# 432.net
KiCad netlist of a schematic drawn in Altium Designer
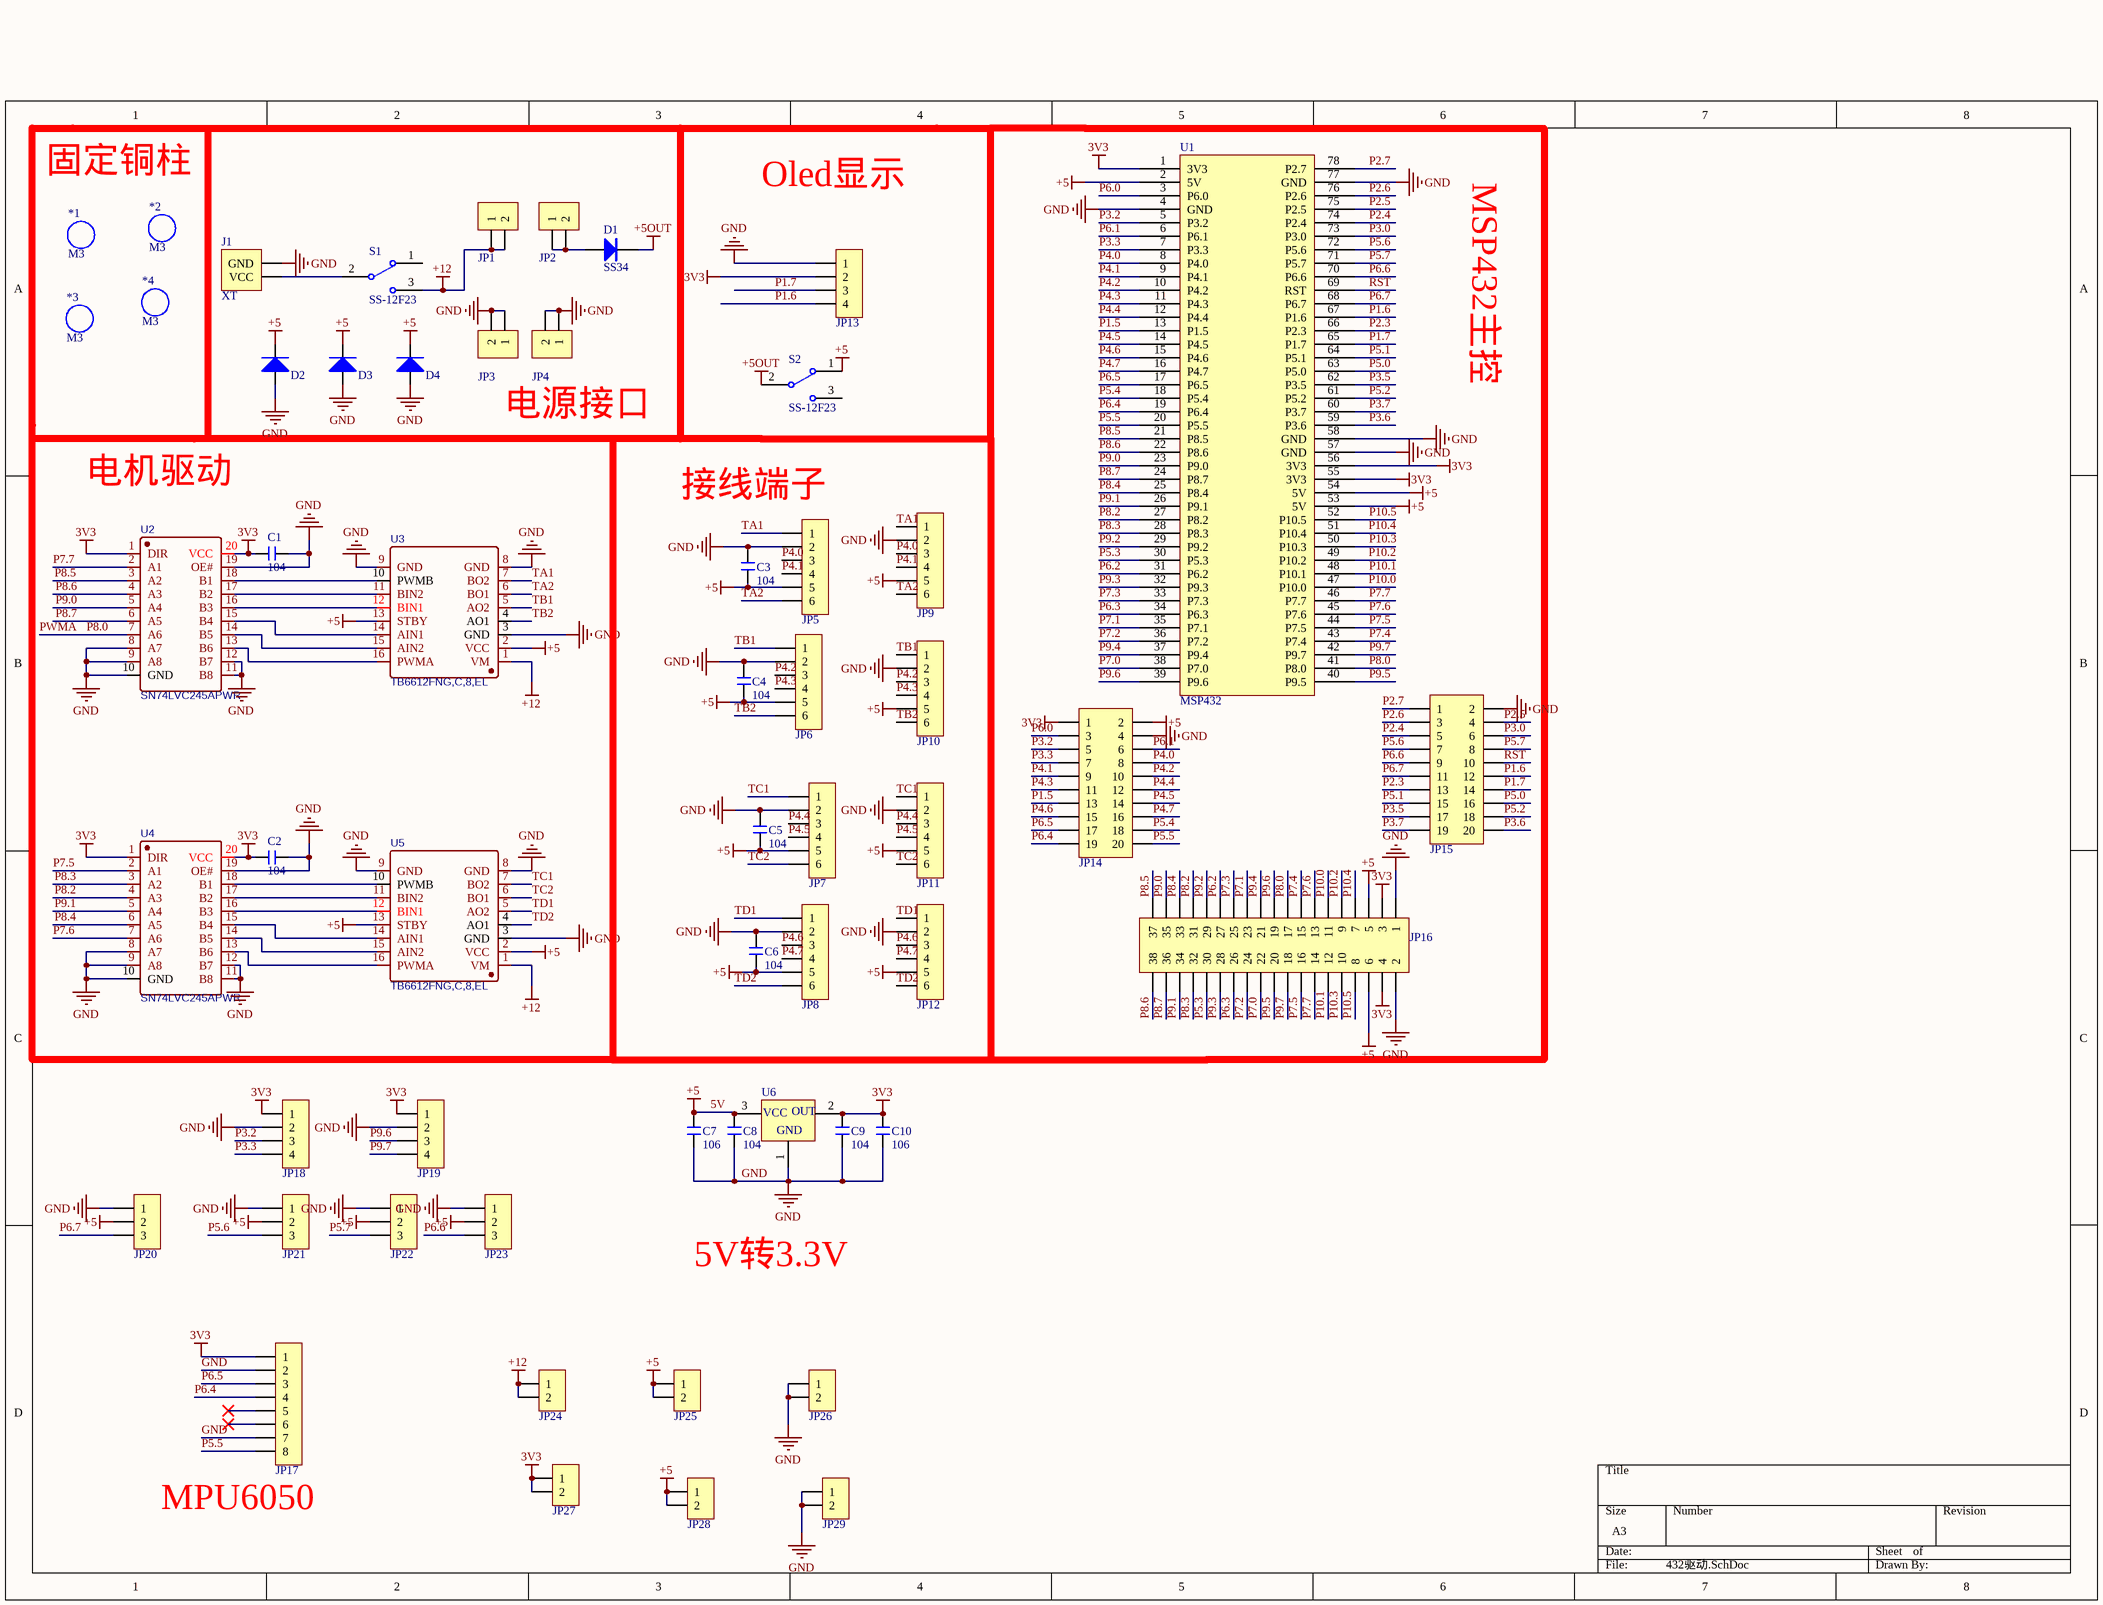
[diagram p0: 432驱动.SchDoc]

(export (version "E")
  (design (tool "Eeschema 10.0.6"))
  (components
    (comp (ref "*1")
      (value "M3")
      (footprint "M3 125X300")
      (description "铜柱孔")
      (fields (field (name "版权归属") "黎明电子style"))
      (libsource (lib "1.7.1-未分类器件") (part "M3"))
    )
    (comp (ref "*2")
      (value "M3")
      (footprint "M3 125X300")
      (description "铜柱孔")
      (fields (field (name "版权归属") "黎明电子style"))
      (libsource (lib "1.7.1-未分类器件") (part "M3"))
    )
    (comp (ref "*3")
      (value "M3")
      (footprint "M3 125X300")
      (description "铜柱孔")
      (fields (field (name "版权归属") "黎明电子style"))
      (libsource (lib "1.7.1-未分类器件") (part "M3"))
    )
    (comp (ref "*4")
      (value "M3")
      (footprint "M3 125X300")
      (description "铜柱孔")
      (fields (field (name "版权归属") "黎明电子style"))
      (libsource (lib "1.7.1-未分类器件") (part "M3"))
    )
    (comp (ref "C1")
      (value "104")
      (footprint "C 0603")
      (description "无极性贴片电容")
      (fields (field (name "版权归属") "黎明电子style"))
      (libsource (lib "1.3.2-电阻_电容_电感") (part "C"))
    )
    (comp (ref "C2")
      (value "104")
      (footprint "C 0603")
      (description "无极性贴片电容")
      (fields (field (name "版权归属") "黎明电子style"))
      (libsource (lib "1.3.2-电阻_电容_电感") (part "C"))
    )
    (comp (ref "C3")
      (value "104")
      (footprint "C 0603_M")
      (description "无极性贴片电容")
      (fields (field (name "版权归属") "黎明电子style"))
      (libsource (lib "1.3.2-电阻_电容_电感") (part "C"))
    )
    (comp (ref "C4")
      (value "104")
      (footprint "C 0603_M")
      (description "无极性贴片电容")
      (fields (field (name "版权归属") "黎明电子style"))
      (libsource (lib "1.3.2-电阻_电容_电感") (part "C"))
    )
    (comp (ref "C5")
      (value "104")
      (footprint "C 0603_M")
      (description "无极性贴片电容")
      (fields (field (name "版权归属") "黎明电子style"))
      (libsource (lib "1.3.2-电阻_电容_电感") (part "C"))
    )
    (comp (ref "C6")
      (value "104")
      (footprint "C 0603_M")
      (description "无极性贴片电容")
      (fields (field (name "版权归属") "黎明电子style"))
      (libsource (lib "1.3.2-电阻_电容_电感") (part "C"))
    )
    (comp (ref "C7")
      (value "106")
      (footprint "C 0805_M")
      (description "贴片电容")
      (libsource (lib "电容") (part "C"))
    )
    (comp (ref "C8")
      (value "104")
      (footprint "C 0805_L")
      (description "贴片电容")
      (libsource (lib "电容") (part "C"))
    )
    (comp (ref "C9")
      (value "104")
      (footprint "C 0805_L")
      (description "贴片电容")
      (libsource (lib "电容") (part "C"))
    )
    (comp (ref "C10")
      (value "106")
      (footprint "C 0805_M")
      (description "贴片电容")
      (libsource (lib "电容") (part "C"))
    )
    (comp (ref "D1")
      (value "SS34")
      (footprint "SMC")
      (description "肖特基二极管")
      (fields (field (name "版权归属") "源创客"))
      (libsource (lib "1.3.3-二极管_整流桥") (part "SS34"))
    )
    (comp (ref "D2")
      (value "TVS")
      (footprint "SMB")
      (description "TVS保护")
      (fields (field (name "PUBLISHER") "Altium Limited"))
      (libsource (lib "二极管") (part "TVS"))
    )
    (comp (ref "D3")
      (value "TVS")
      (footprint "SMB")
      (description "TVS保护")
      (fields (field (name "PUBLISHER") "Altium Limited"))
      (libsource (lib "二极管") (part "TVS"))
    )
    (comp (ref "D4")
      (value "TVS")
      (footprint "SMB")
      (description "TVS保护")
      (fields (field (name "PUBLISHER") "Altium Limited"))
      (libsource (lib "二极管") (part "TVS"))
    )
    (comp (ref "J1")
      (value "XT")
      (footprint "T-SET")
      (description "航模电池接口")
      (libsource (lib "1.5.3-接口类") (part "XT"))
    )
    (comp (ref "JP1")
      (value "HDR-1X2")
      (footprint "HDR2.54-M-LI-2P")
      (description "2P接插件")
      (fields (field (name "版权归属") "黎明电子style"))
      (libsource (lib "") (part "Header 2_2"))
    )
    (comp (ref "JP2")
      (value "HDR-1X2")
      (footprint "HDR2.54-M-LI-2P")
      (description "2P接插件")
      (fields (field (name "版权归属") "黎明电子style"))
      (libsource (lib "") (part "Header 2_2"))
    )
    (comp (ref "JP3")
      (value "HDR-1X2")
      (footprint "HDR2.54-M-LI-2P")
      (description "2P接插件")
      (fields (field (name "版权归属") "黎明电子style"))
      (libsource (lib "") (part "Header 2_1"))
    )
    (comp (ref "JP4")
      (value "HDR-1X2")
      (footprint "HDR2.54-M-LI-2P")
      (description "2P接插件")
      (fields (field (name "版权归属") "黎明电子style"))
      (libsource (lib "") (part "Header 2_1"))
    )
    (comp (ref "JP5")
      (value "HDR-1X6")
      (footprint "PH2.0-WI-6P")
      (description "6P接插件")
      (fields (field (name "版权归属") "源创客"))
      (libsource (lib "4.4   - 接插件-脚距2.0") (part "Header 6"))
    )
    (comp (ref "JP6")
      (value "HDR-1X6")
      (footprint "PH2.0-WI-6P")
      (description "6P接插件")
      (fields (field (name "版权归属") "源创客"))
      (libsource (lib "4.4   - 接插件-脚距2.0") (part "Header 6"))
    )
    (comp (ref "JP7")
      (value "HDR-1X6")
      (footprint "PH2.0-WI-6P")
      (description "6P接插件")
      (fields (field (name "版权归属") "源创客"))
      (libsource (lib "4.4   - 接插件-脚距2.0") (part "Header 6"))
    )
    (comp (ref "JP8")
      (value "HDR-1X6")
      (footprint "PH2.0-WI-6P")
      (description "6P接插件")
      (fields (field (name "版权归属") "源创客"))
      (libsource (lib "4.4   - 接插件-脚距2.0") (part "Header 6"))
    )
    (comp (ref "JP9")
      (value "HDR-1X6")
      (footprint "XH2.54-WI-6P")
      (description "6P接插件")
      (fields (field (name "版权归属") "黎明电子style"))
      (libsource (lib "1.5.1-接插件") (part "Header 6"))
    )
    (comp (ref "JP10")
      (value "HDR-1X6")
      (footprint "XH2.54-WI-6P")
      (description "6P接插件")
      (fields (field (name "版权归属") "黎明电子style"))
      (libsource (lib "1.5.1-接插件") (part "Header 6"))
    )
    (comp (ref "JP11")
      (value "HDR-1X6")
      (footprint "XH2.54-WI-6P")
      (description "6P接插件")
      (fields (field (name "版权归属") "黎明电子style"))
      (libsource (lib "1.5.1-接插件") (part "Header 6"))
    )
    (comp (ref "JP12")
      (value "HDR-1X6")
      (footprint "XH2.54-WI-6P")
      (description "6P接插件")
      (fields (field (name "版权归属") "黎明电子style"))
      (libsource (lib "1.5.1-接插件") (part "Header 6"))
    )
    (comp (ref "JP13")
      (value "HDR-1X4")
      (footprint "HDR2.54-M-LI-4P")
      (description "4P接插件")
      (fields (field (name "版权归属") "封装库来自淘宝 ID：黄晶宝石"))
      (libsource (lib "接插件-2.54MM") (part "Header 4"))
    )
    (comp (ref "JP14")
      (value "Header 2X10")
      (footprint "HDR2.54-LI-2x10P")
      (description "10*2P接插件")
      (fields (field (name "版权归属") "源创客"))
      (libsource (lib "接插件-2.54MM") (part "Header 10X2"))
    )
    (comp (ref "JP15")
      (value "Header 2X10")
      (footprint "HDR2.54-LI-2x10P")
      (description "10*2P接插件")
      (fields (field (name "版权归属") "源创客"))
      (libsource (lib "接插件-2.54MM") (part "Header 10X2"))
    )
    (comp (ref "JP16")
      (value "Header 2X11")
      (footprint "HDR2.54-LI-2x19P")
      (description "19*2P接插件")
      (fields (field (name "版权归属") "封装库来自淘宝 ID：黄晶宝石"))
      (libsource (lib "接插件-2.54MM") (part "Header 19X2"))
    )
    (comp (ref "JP17")
      (value "HDR-1X8")
      (footprint "HDR2.54-M-LI-8P")
      (description "8P接插件")
      (fields (field (name "版权归属") "封装库来自淘宝 ID：黄晶宝石"))
      (libsource (lib "接插件-2.54MM") (part "Header 8"))
    )
    (comp (ref "JP18")
      (value "HDR-1X4")
      (footprint "HDR2.54-LI-4P")
      (description "4P接插件")
      (fields (field (name "版权归属") "封装库来自淘宝 ID：黄晶宝石"))
      (libsource (lib "接插件-2.54MM") (part "Header 4"))
    )
    (comp (ref "JP19")
      (value "HDR-1X4")
      (footprint "HDR2.54-LI-4P")
      (description "4P接插件")
      (fields (field (name "版权归属") "封装库来自淘宝 ID：黄晶宝石"))
      (libsource (lib "接插件-2.54MM") (part "Header 4"))
    )
    (comp (ref "JP20")
      (value "HDR-1X3")
      (footprint "HDR2.54-LI-3P")
      (description "3P接插件")
      (fields (field (name "版权归属") "封装库来自淘宝 ID：黄晶宝石"))
      (libsource (lib "接插件-2.54MM") (part "Header 3"))
    )
    (comp (ref "JP21")
      (value "HDR-1X3")
      (footprint "HDR2.54-LI-3P")
      (description "3P接插件")
      (fields (field (name "版权归属") "封装库来自淘宝 ID：黄晶宝石"))
      (libsource (lib "接插件-2.54MM") (part "Header 3"))
    )
    (comp (ref "JP22")
      (value "HDR-1X3")
      (footprint "HDR2.54-LI-3P")
      (description "3P接插件")
      (fields (field (name "版权归属") "封装库来自淘宝 ID：黄晶宝石"))
      (libsource (lib "接插件-2.54MM") (part "Header 3"))
    )
    (comp (ref "JP23")
      (value "HDR-1X3")
      (footprint "HDR2.54-LI-3P")
      (description "3P接插件")
      (fields (field (name "版权归属") "封装库来自淘宝 ID：黄晶宝石"))
      (libsource (lib "接插件-2.54MM") (part "Header 3"))
    )
    (comp (ref "JP24")
      (value "HDR-1X2")
      (footprint "HDR2.54-M-LI-2P")
      (description "2P接插件")
      (fields (field (name "版权归属") "黎明电子style"))
      (libsource (lib "1.5.1-接插件") (part "Header 2"))
    )
    (comp (ref "JP25")
      (value "HDR-1X2")
      (footprint "HDR2.54-M-LI-2P")
      (description "2P接插件")
      (fields (field (name "版权归属") "黎明电子style"))
      (libsource (lib "1.5.1-接插件") (part "Header 2"))
    )
    (comp (ref "JP26")
      (value "HDR-1X2")
      (footprint "HDR2.54-M-LI-2P")
      (description "2P接插件")
      (fields (field (name "版权归属") "黎明电子style"))
      (libsource (lib "1.5.1-接插件") (part "Header 2"))
    )
    (comp (ref "JP27")
      (value "HDR-1X2")
      (footprint "HDR2.54-M-LI-2P")
      (description "2P接插件")
      (fields (field (name "版权归属") "黎明电子style"))
      (libsource (lib "1.5.1-接插件") (part "Header 2"))
    )
    (comp (ref "JP28")
      (value "HDR-1X2")
      (footprint "HDR2.54-M-LI-2P")
      (description "2P接插件")
      (fields (field (name "版权归属") "黎明电子style"))
      (libsource (lib "1.5.1-接插件") (part "Header 2"))
    )
    (comp (ref "JP29")
      (value "HDR-1X2")
      (footprint "HDR2.54-M-LI-2P")
      (description "2P接插件")
      (fields (field (name "版权归属") "黎明电子style"))
      (libsource (lib "1.5.1-接插件") (part "Header 2"))
    )
    (comp (ref "S1")
      (value "SS-12F23")
      (footprint "SS-12F23")
      (description "1路波动开关")
      (fields (field (name "版权归属") "黎明电子style"))
      (libsource (lib "1.4.1-按键-开关") (part "SSW-1P"))
    )
    (comp (ref "S2")
      (value "SS-12F23")
      (footprint "SS-12F23")
      (description "1路波动开关")
      (fields (field (name "版权归属") "黎明电子style"))
      (libsource (lib "1.4.1-按键-开关") (part "SSW-1P"))
    )
    (comp (ref "U1")
      (value "MSP432")
      (footprint "msp432")
      (description "适配msp432官方")
      (libsource (lib "主控板") (part "MSP432"))
    )
    (comp (ref "U2")
      (value "SN74LVC245APWR")
      (footprint "TTSOP")
      (fields (field (name "BOM_SUPPLIER PART") "C7848"))
      (libsource (lib "74lvc245") (part "SN74LVC245APWR"))
    )
    (comp (ref "U3")
      (value "TB6612FNG,C,8,EL")
      (footprint "PCBComponent_1 - duplicate")
      (fields (field (name "BOM_SUPPLIER PART") "C141517") (field (name "CONTRIBUTOR") "LCSC"))
      (libsource (lib "TB6612") (part "TB6612FNG,C,8,EL"))
    )
    (comp (ref "U4")
      (value "SN74LVC245APWR")
      (footprint "TTSOP")
      (fields (field (name "BOM_SUPPLIER PART") "C7848"))
      (libsource (lib "74lvc245") (part "SN74LVC245APWR"))
    )
    (comp (ref "U5")
      (value "TB6612FNG,C,8,EL")
      (footprint "PCBComponent_1 - duplicate")
      (fields (field (name "BOM_SUPPLIER PART") "C141517") (field (name "CONTRIBUTOR") "LCSC"))
      (libsource (lib "TB6612") (part "TB6612FNG,C,8,EL"))
    )
    (comp (ref "U6") (value "~") (footprint "SOT-223") (libsource (lib "Schlib1") (part "Component_1")))
  )
  (nets
    (net (code "1") (name "+5") (class "Default")
      (node (ref "C3") (pin "1") (pinfunction "1_1") (pintype "passive"))
      (node (ref "C4") (pin "1") (pinfunction "1_1") (pintype "passive"))
      (node (ref "C5") (pin "1") (pinfunction "1_1") (pintype "passive"))
      (node (ref "C6") (pin "1") (pinfunction "1_1") (pintype "passive"))
      (node (ref "C7") (pin "2") (pinfunction "2_2") (pintype "passive"))
      (node (ref "C8") (pin "2") (pinfunction "2_2") (pintype "passive"))
      (node (ref "D2") (pin "2") (pinfunction "K_2") (pintype "passive"))
      (node (ref "D3") (pin "2") (pinfunction "K_2") (pintype "passive"))
      (node (ref "D4") (pin "2") (pinfunction "K_2") (pintype "passive"))
      (node (ref "JP10") (pin "5") (pinfunction "5_5") (pintype "passive"))
      (node (ref "JP11") (pin "5") (pinfunction "5_5") (pintype "passive"))
      (node (ref "JP12") (pin "5") (pinfunction "5_5") (pintype "passive"))
      (node (ref "JP14") (pin "2") (pinfunction "2_2") (pintype "passive"))
      (node (ref "JP16") (pin "5") (pinfunction "5_5") (pintype "passive"))
      (node (ref "JP16") (pin "6") (pinfunction "6_6") (pintype "passive"))
      (node (ref "JP20") (pin "2") (pinfunction "2_2") (pintype "passive"))
      (node (ref "JP21") (pin "2") (pinfunction "2_2") (pintype "passive"))
      (node (ref "JP22") (pin "2") (pinfunction "2_2") (pintype "passive"))
      (node (ref "JP23") (pin "2") (pinfunction "2_2") (pintype "passive"))
      (node (ref "JP25") (pin "1") (pinfunction "1_1") (pintype "passive"))
      (node (ref "JP25") (pin "2") (pinfunction "2_2") (pintype "passive"))
      (node (ref "JP28") (pin "1") (pinfunction "1_1") (pintype "passive"))
      (node (ref "JP28") (pin "2") (pinfunction "2_2") (pintype "passive"))
      (node (ref "JP5") (pin "5") (pinfunction "5_5") (pintype "passive"))
      (node (ref "JP6") (pin "5") (pinfunction "5_5") (pintype "passive"))
      (node (ref "JP7") (pin "5") (pinfunction "5_5") (pintype "passive"))
      (node (ref "JP8") (pin "5") (pinfunction "5_5") (pintype "passive"))
      (node (ref "JP9") (pin "5") (pinfunction "5_5") (pintype "passive"))
      (node (ref "S2") (pin "1") (pinfunction "1_1") (pintype "passive"))
      (node (ref "U1") (pin "2") (pinfunction "5V_2") (pintype "passive"))
      (node (ref "U1") (pin "53") (pinfunction "5V_53") (pintype "passive"))
      (node (ref "U1") (pin "54") (pinfunction "5V_54") (pintype "passive"))
      (node (ref "U3") (pin "13") (pinfunction "STBY_13") (pintype "passive"))
      (node (ref "U3") (pin "2") (pinfunction "VCC_2") (pintype "passive"))
      (node (ref "U5") (pin "13") (pinfunction "STBY_13") (pintype "passive"))
      (node (ref "U5") (pin "2") (pinfunction "VCC_2") (pintype "passive"))
      (node (ref "U6") (pin "3") (pinfunction "3_3") (pintype "passive"))
    )
    (net (code "2") (name "+5OUT") (class "Default")
      (node (ref "D1") (pin "2") (pinfunction "K_2") (pintype "passive"))
      (node (ref "S2") (pin "2") (pinfunction "2_2") (pintype "passive"))
    )
    (net (code "3") (name "+12") (class "Default")
      (node (ref "JP1") (pin "1") (pinfunction "1_1") (pintype "passive"))
      (node (ref "JP1") (pin "2") (pinfunction "2_2") (pintype "passive"))
      (node (ref "JP24") (pin "1") (pinfunction "1_1") (pintype "passive"))
      (node (ref "JP24") (pin "2") (pinfunction "2_2") (pintype "passive"))
      (node (ref "S1") (pin "3") (pinfunction "3_3") (pintype "passive"))
      (node (ref "U3") (pin "1") (pinfunction "VM_1") (pintype "passive"))
      (node (ref "U5") (pin "1") (pinfunction "VM_1") (pintype "passive"))
    )
    (net (code "4") (name "/P1.5") (class "Default")
      (node (ref "JP14") (pin "13") (pinfunction "13_13") (pintype "passive"))
      (node (ref "U1") (pin "13") (pinfunction "P1.5_13") (pintype "passive"))
    )
    (net (code "5") (name "/P1.6") (class "Default")
      (node (ref "JP13") (pin "4") (pinfunction "4_4") (pintype "passive"))
      (node (ref "JP15") (pin "12") (pinfunction "12_12") (pintype "passive"))
      (node (ref "U1") (pin "67") (pinfunction "P1.6_67") (pintype "passive"))
    )
    (net (code "6") (name "/P1.7") (class "Default")
      (node (ref "JP13") (pin "3") (pinfunction "3_3") (pintype "passive"))
      (node (ref "JP15") (pin "14") (pinfunction "14_14") (pintype "passive"))
      (node (ref "U1") (pin "65") (pinfunction "P1.7_65") (pintype "passive"))
    )
    (net (code "7") (name "/P2.3") (class "Default")
      (node (ref "JP15") (pin "13") (pinfunction "13_13") (pintype "passive"))
      (node (ref "U1") (pin "66") (pinfunction "P2.3_66") (pintype "passive"))
    )
    (net (code "8") (name "/P2.4") (class "Default")
      (node (ref "JP15") (pin "5") (pinfunction "5_5") (pintype "passive"))
      (node (ref "U1") (pin "74") (pinfunction "P2.4_74") (pintype "passive"))
    )
    (net (code "9") (name "/P2.5") (class "Default")
      (node (ref "JP15") (pin "4") (pinfunction "4_4") (pintype "passive"))
      (node (ref "U1") (pin "75") (pinfunction "P2.5_75") (pintype "passive"))
    )
    (net (code "10") (name "/P2.6") (class "Default")
      (node (ref "JP15") (pin "3") (pinfunction "3_3") (pintype "passive"))
      (node (ref "U1") (pin "76") (pinfunction "P2.6_76") (pintype "passive"))
    )
    (net (code "11") (name "/P2.7") (class "Default")
      (node (ref "JP15") (pin "1") (pinfunction "1_1") (pintype "passive"))
      (node (ref "U1") (pin "78") (pinfunction "P2.7_78") (pintype "passive"))
    )
    (net (code "12") (name "/P3.0") (class "Default")
      (node (ref "JP15") (pin "6") (pinfunction "6_6") (pintype "passive"))
      (node (ref "U1") (pin "73") (pinfunction "P3.0_73") (pintype "passive"))
    )
    (net (code "13") (name "/P3.2") (class "Default")
      (node (ref "JP14") (pin "5") (pinfunction "5_5") (pintype "passive"))
      (node (ref "JP18") (pin "3") (pinfunction "3_3") (pintype "passive"))
      (node (ref "U1") (pin "5") (pinfunction "P3.2_5") (pintype "passive"))
    )
    (net (code "14") (name "/P3.3") (class "Default")
      (node (ref "JP14") (pin "7") (pinfunction "7_7") (pintype "passive"))
      (node (ref "JP18") (pin "4") (pinfunction "4_4") (pintype "passive"))
      (node (ref "U1") (pin "7") (pinfunction "P3.3_7") (pintype "passive"))
    )
    (net (code "15") (name "/P3.5") (class "Default")
      (node (ref "JP15") (pin "17") (pinfunction "17_17") (pintype "passive"))
      (node (ref "U1") (pin "62") (pinfunction "P3.5_62") (pintype "passive"))
    )
    (net (code "16") (name "/P3.6") (class "Default")
      (node (ref "JP15") (pin "20") (pinfunction "20_20") (pintype "passive"))
      (node (ref "U1") (pin "59") (pinfunction "P3.6_59") (pintype "passive"))
    )
    (net (code "17") (name "/P3.7") (class "Default")
      (node (ref "JP15") (pin "19") (pinfunction "19_19") (pintype "passive"))
      (node (ref "U1") (pin "60") (pinfunction "P3.7_60") (pintype "passive"))
    )
    (net (code "18") (name "/P4.0") (class "Default")
      (node (ref "JP14") (pin "8") (pinfunction "8_8") (pintype "passive"))
      (node (ref "JP5") (pin "3") (pinfunction "3_3") (pintype "passive"))
      (node (ref "JP9") (pin "3") (pinfunction "3_3") (pintype "passive"))
      (node (ref "U1") (pin "8") (pinfunction "P4.0_8") (pintype "passive"))
    )
    (net (code "19") (name "/P4.1") (class "Default")
      (node (ref "JP14") (pin "9") (pinfunction "9_9") (pintype "passive"))
      (node (ref "JP5") (pin "4") (pinfunction "4_4") (pintype "passive"))
      (node (ref "JP9") (pin "4") (pinfunction "4_4") (pintype "passive"))
      (node (ref "U1") (pin "9") (pinfunction "P4.1_9") (pintype "passive"))
    )
    (net (code "20") (name "/P4.2") (class "Default")
      (node (ref "JP10") (pin "3") (pinfunction "3_3") (pintype "passive"))
      (node (ref "JP14") (pin "10") (pinfunction "10_10") (pintype "passive"))
      (node (ref "JP6") (pin "3") (pinfunction "3_3") (pintype "passive"))
      (node (ref "U1") (pin "10") (pinfunction "P4.2_10") (pintype "passive"))
    )
    (net (code "21") (name "/P4.3") (class "Default")
      (node (ref "JP10") (pin "4") (pinfunction "4_4") (pintype "passive"))
      (node (ref "JP14") (pin "11") (pinfunction "11_11") (pintype "passive"))
      (node (ref "JP6") (pin "4") (pinfunction "4_4") (pintype "passive"))
      (node (ref "U1") (pin "11") (pinfunction "P4.3_11") (pintype "passive"))
    )
    (net (code "22") (name "/P4.4") (class "Default")
      (node (ref "JP11") (pin "3") (pinfunction "3_3") (pintype "passive"))
      (node (ref "JP14") (pin "12") (pinfunction "12_12") (pintype "passive"))
      (node (ref "JP7") (pin "3") (pinfunction "3_3") (pintype "passive"))
      (node (ref "U1") (pin "12") (pinfunction "P4.4_12") (pintype "passive"))
    )
    (net (code "23") (name "/P4.5") (class "Default")
      (node (ref "JP11") (pin "4") (pinfunction "4_4") (pintype "passive"))
      (node (ref "JP14") (pin "14") (pinfunction "14_14") (pintype "passive"))
      (node (ref "JP7") (pin "4") (pinfunction "4_4") (pintype "passive"))
      (node (ref "U1") (pin "14") (pinfunction "P4.5_14") (pintype "passive"))
    )
    (net (code "24") (name "/P4.6") (class "Default")
      (node (ref "JP12") (pin "3") (pinfunction "3_3") (pintype "passive"))
      (node (ref "JP14") (pin "15") (pinfunction "15_15") (pintype "passive"))
      (node (ref "JP8") (pin "3") (pinfunction "3_3") (pintype "passive"))
      (node (ref "U1") (pin "15") (pinfunction "P4.6_15") (pintype "passive"))
    )
    (net (code "25") (name "/P4.7") (class "Default")
      (node (ref "JP12") (pin "4") (pinfunction "4_4") (pintype "passive"))
      (node (ref "JP14") (pin "16") (pinfunction "16_16") (pintype "passive"))
      (node (ref "JP8") (pin "4") (pinfunction "4_4") (pintype "passive"))
      (node (ref "U1") (pin "16") (pinfunction "P4.7_16") (pintype "passive"))
    )
    (net (code "26") (name "/P5.0") (class "Default")
      (node (ref "JP15") (pin "16") (pinfunction "16_16") (pintype "passive"))
      (node (ref "U1") (pin "63") (pinfunction "P5.0_63") (pintype "passive"))
    )
    (net (code "27") (name "/P5.1") (class "Default")
      (node (ref "JP15") (pin "15") (pinfunction "15_15") (pintype "passive"))
      (node (ref "U1") (pin "64") (pinfunction "P5.1_64") (pintype "passive"))
    )
    (net (code "28") (name "/P5.2") (class "Default")
      (node (ref "JP15") (pin "18") (pinfunction "18_18") (pintype "passive"))
      (node (ref "U1") (pin "61") (pinfunction "P5.2_61") (pintype "passive"))
    )
    (net (code "29") (name "/P5.3") (class "Default")
      (node (ref "JP16") (pin "30") (pinfunction "30_30") (pintype "passive"))
      (node (ref "U1") (pin "30") (pinfunction "P5.3_30") (pintype "passive"))
    )
    (net (code "30") (name "/P5.4") (class "Default")
      (node (ref "JP14") (pin "18") (pinfunction "18_18") (pintype "passive"))
      (node (ref "U1") (pin "18") (pinfunction "P5.4_18") (pintype "passive"))
    )
    (net (code "31") (name "/P5.5") (class "Default")
      (node (ref "JP14") (pin "20") (pinfunction "20_20") (pintype "passive"))
      (node (ref "JP17") (pin "8") (pinfunction "8_8") (pintype "passive"))
      (node (ref "U1") (pin "20") (pinfunction "P5.5_20") (pintype "passive"))
    )
    (net (code "32") (name "/P5.6") (class "Default")
      (node (ref "JP15") (pin "7") (pinfunction "7_7") (pintype "passive"))
      (node (ref "JP21") (pin "3") (pinfunction "3_3") (pintype "passive"))
      (node (ref "U1") (pin "72") (pinfunction "P5.6_72") (pintype "passive"))
    )
    (net (code "33") (name "/P5.7") (class "Default")
      (node (ref "JP15") (pin "8") (pinfunction "8_8") (pintype "passive"))
      (node (ref "JP22") (pin "3") (pinfunction "3_3") (pintype "passive"))
      (node (ref "U1") (pin "71") (pinfunction "P5.7_71") (pintype "passive"))
    )
    (net (code "34") (name "/P6.0") (class "Default")
      (node (ref "JP14") (pin "3") (pinfunction "3_3") (pintype "passive"))
      (node (ref "U1") (pin "3") (pinfunction "P6.0_3") (pintype "passive"))
    )
    (net (code "35") (name "/P6.1") (class "Default")
      (node (ref "JP14") (pin "6") (pinfunction "6_6") (pintype "passive"))
      (node (ref "U1") (pin "6") (pinfunction "P6.1_6") (pintype "passive"))
    )
    (net (code "36") (name "/P6.2") (class "Default")
      (node (ref "JP16") (pin "27") (pinfunction "27_27") (pintype "passive"))
      (node (ref "U1") (pin "31") (pinfunction "P6.2_31") (pintype "passive"))
    )
    (net (code "37") (name "/P6.3") (class "Default")
      (node (ref "JP16") (pin "26") (pinfunction "26_26") (pintype "passive"))
      (node (ref "U1") (pin "34") (pinfunction "P6.3_34") (pintype "passive"))
    )
    (net (code "38") (name "/P6.4") (class "Default")
      (node (ref "JP14") (pin "19") (pinfunction "19_19") (pintype "passive"))
      (node (ref "JP17") (pin "4") (pinfunction "4_4") (pintype "passive"))
      (node (ref "U1") (pin "19") (pinfunction "P6.4_19") (pintype "passive"))
    )
    (net (code "39") (name "/P6.5") (class "Default")
      (node (ref "JP14") (pin "17") (pinfunction "17_17") (pintype "passive"))
      (node (ref "JP17") (pin "3") (pinfunction "3_3") (pintype "passive"))
      (node (ref "U1") (pin "17") (pinfunction "P6.5_17") (pintype "passive"))
    )
    (net (code "40") (name "/P6.6") (class "Default")
      (node (ref "JP15") (pin "9") (pinfunction "9_9") (pintype "passive"))
      (node (ref "JP23") (pin "3") (pinfunction "3_3") (pintype "passive"))
      (node (ref "U1") (pin "70") (pinfunction "P6.6_70") (pintype "passive"))
    )
    (net (code "41") (name "/P6.7") (class "Default")
      (node (ref "JP15") (pin "11") (pinfunction "11_11") (pintype "passive"))
      (node (ref "JP20") (pin "3") (pinfunction "3_3") (pintype "passive"))
      (node (ref "U1") (pin "68") (pinfunction "P6.7_68") (pintype "passive"))
    )
    (net (code "42") (name "/P7.0") (class "Default")
      (node (ref "JP16") (pin "22") (pinfunction "22_22") (pintype "passive"))
      (node (ref "U1") (pin "38") (pinfunction "P7.0_38") (pintype "passive"))
    )
    (net (code "43") (name "/P7.1") (class "Default")
      (node (ref "JP16") (pin "23") (pinfunction "23_23") (pintype "passive"))
      (node (ref "U1") (pin "35") (pinfunction "P7.1_35") (pintype "passive"))
    )
    (net (code "44") (name "/P7.2") (class "Default")
      (node (ref "JP16") (pin "24") (pinfunction "24_24") (pintype "passive"))
      (node (ref "U1") (pin "36") (pinfunction "P7.2_36") (pintype "passive"))
    )
    (net (code "45") (name "/P7.3") (class "Default")
      (node (ref "JP16") (pin "25") (pinfunction "25_25") (pintype "passive"))
      (node (ref "U1") (pin "33") (pinfunction "P7.3_33") (pintype "passive"))
    )
    (net (code "46") (name "/P7.4") (class "Default")
      (node (ref "JP16") (pin "15") (pinfunction "15_15") (pintype "passive"))
      (node (ref "U1") (pin "43") (pinfunction "P7.4_43") (pintype "passive"))
    )
    (net (code "47") (name "/P7.5") (class "Default")
      (node (ref "JP16") (pin "16") (pinfunction "16_16") (pintype "passive"))
      (node (ref "U1") (pin "44") (pinfunction "P7.5_44") (pintype "passive"))
      (node (ref "U4") (pin "2") (pinfunction "A1_2") (pintype "passive"))
    )
    (net (code "48") (name "/P7.6") (class "Default")
      (node (ref "JP16") (pin "13") (pinfunction "13_13") (pintype "passive"))
      (node (ref "U1") (pin "45") (pinfunction "P7.6_45") (pintype "passive"))
      (node (ref "U4") (pin "7") (pinfunction "A6_7") (pintype "passive"))
    )
    (net (code "49") (name "/P7.7") (class "Default")
      (node (ref "JP16") (pin "14") (pinfunction "14_14") (pintype "passive"))
      (node (ref "U1") (pin "46") (pinfunction "P7.7_46") (pintype "passive"))
      (node (ref "U2") (pin "2") (pinfunction "A1_2") (pintype "passive"))
    )
    (net (code "50") (name "/P8.0") (class "Default")
      (node (ref "JP16") (pin "17") (pinfunction "17_17") (pintype "passive"))
      (node (ref "U1") (pin "41") (pinfunction "P8.0_41") (pintype "passive"))
      (node (ref "U2") (pin "7") (pinfunction "A6_7") (pintype "passive"))
    )
    (net (code "51") (name "/P8.2") (class "Default")
      (node (ref "JP16") (pin "31") (pinfunction "31_31") (pintype "passive"))
      (node (ref "U1") (pin "27") (pinfunction "P8.2_27") (pintype "passive"))
      (node (ref "U4") (pin "4") (pinfunction "A3_4") (pintype "passive"))
    )
    (net (code "52") (name "/P8.3") (class "Default")
      (node (ref "JP16") (pin "32") (pinfunction "32_32") (pintype "passive"))
      (node (ref "U1") (pin "28") (pinfunction "P8.3_28") (pintype "passive"))
      (node (ref "U4") (pin "3") (pinfunction "A2_3") (pintype "passive"))
    )
    (net (code "53") (name "/P8.4") (class "Default")
      (node (ref "JP16") (pin "33") (pinfunction "33_33") (pintype "passive"))
      (node (ref "U1") (pin "25") (pinfunction "P8.4_25") (pintype "passive"))
      (node (ref "U4") (pin "6") (pinfunction "A5_6") (pintype "passive"))
    )
    (net (code "54") (name "/P8.5") (class "Default")
      (node (ref "JP16") (pin "37") (pinfunction "37_37") (pintype "passive"))
      (node (ref "U1") (pin "21") (pinfunction "P8.5_21") (pintype "passive"))
      (node (ref "U2") (pin "3") (pinfunction "A2_3") (pintype "passive"))
    )
    (net (code "55") (name "/P8.6") (class "Default")
      (node (ref "JP16") (pin "38") (pinfunction "38_38") (pintype "passive"))
      (node (ref "U1") (pin "22") (pinfunction "P8.6_22") (pintype "passive"))
      (node (ref "U2") (pin "4") (pinfunction "A3_4") (pintype "passive"))
    )
    (net (code "56") (name "/P8.7") (class "Default")
      (node (ref "JP16") (pin "36") (pinfunction "36_36") (pintype "passive"))
      (node (ref "U1") (pin "24") (pinfunction "P8.7_24") (pintype "passive"))
      (node (ref "U2") (pin "6") (pinfunction "A5_6") (pintype "passive"))
    )
    (net (code "57") (name "/P9.0") (class "Default")
      (node (ref "JP16") (pin "35") (pinfunction "35_35") (pintype "passive"))
      (node (ref "U1") (pin "23") (pinfunction "P9.0_23") (pintype "passive"))
      (node (ref "U2") (pin "5") (pinfunction "A4_5") (pintype "passive"))
    )
    (net (code "58") (name "/P9.1") (class "Default")
      (node (ref "JP16") (pin "34") (pinfunction "34_34") (pintype "passive"))
      (node (ref "U1") (pin "26") (pinfunction "P9.1_26") (pintype "passive"))
      (node (ref "U4") (pin "5") (pinfunction "A4_5") (pintype "passive"))
    )
    (net (code "59") (name "/P9.2") (class "Default")
      (node (ref "JP16") (pin "29") (pinfunction "29_29") (pintype "passive"))
      (node (ref "U1") (pin "29") (pinfunction "P9.2_29") (pintype "passive"))
    )
    (net (code "60") (name "/P9.3") (class "Default")
      (node (ref "JP16") (pin "28") (pinfunction "28_28") (pintype "passive"))
      (node (ref "U1") (pin "32") (pinfunction "P9.3_32") (pintype "passive"))
    )
    (net (code "61") (name "/P9.4") (class "Default")
      (node (ref "JP16") (pin "21") (pinfunction "21_21") (pintype "passive"))
      (node (ref "U1") (pin "37") (pinfunction "P9.4_37") (pintype "passive"))
    )
    (net (code "62") (name "/P9.5") (class "Default")
      (node (ref "JP16") (pin "20") (pinfunction "20_20") (pintype "passive"))
      (node (ref "U1") (pin "40") (pinfunction "P9.5_40") (pintype "passive"))
    )
    (net (code "63") (name "/P9.6") (class "Default")
      (node (ref "JP16") (pin "19") (pinfunction "19_19") (pintype "passive"))
      (node (ref "JP19") (pin "3") (pinfunction "3_3") (pintype "passive"))
      (node (ref "U1") (pin "39") (pinfunction "P9.6_39") (pintype "passive"))
    )
    (net (code "64") (name "/P9.7") (class "Default")
      (node (ref "JP16") (pin "18") (pinfunction "18_18") (pintype "passive"))
      (node (ref "JP19") (pin "4") (pinfunction "4_4") (pintype "passive"))
      (node (ref "U1") (pin "42") (pinfunction "P9.7_42") (pintype "passive"))
    )
    (net (code "65") (name "/P10.0") (class "Default")
      (node (ref "JP16") (pin "11") (pinfunction "11_11") (pintype "passive"))
      (node (ref "U1") (pin "47") (pinfunction "P10.0_47") (pintype "passive"))
    )
    (net (code "66") (name "/P10.1") (class "Default")
      (node (ref "JP16") (pin "12") (pinfunction "12_12") (pintype "passive"))
      (node (ref "U1") (pin "48") (pinfunction "P10.1_48") (pintype "passive"))
    )
    (net (code "67") (name "/P10.2") (class "Default")
      (node (ref "JP16") (pin "9") (pinfunction "9_9") (pintype "passive"))
      (node (ref "U1") (pin "49") (pinfunction "P10.2_49") (pintype "passive"))
    )
    (net (code "68") (name "/P10.3") (class "Default")
      (node (ref "JP16") (pin "10") (pinfunction "10_10") (pintype "passive"))
      (node (ref "U1") (pin "50") (pinfunction "P10.3_50") (pintype "passive"))
    )
    (net (code "69") (name "/P10.4") (class "Default")
      (node (ref "JP16") (pin "7") (pinfunction "7_7") (pintype "passive"))
      (node (ref "U1") (pin "51") (pinfunction "P10.4_51") (pintype "passive"))
    )
    (net (code "70") (name "/P10.5") (class "Default")
      (node (ref "JP16") (pin "8") (pinfunction "8_8") (pintype "passive"))
      (node (ref "U1") (pin "52") (pinfunction "P10.5_52") (pintype "passive"))
    )
    (net (code "71") (name "/RST") (class "Default")
      (node (ref "JP15") (pin "10") (pinfunction "10_10") (pintype "passive"))
      (node (ref "U1") (pin "69") (pinfunction "RST_69") (pintype "passive"))
    )
    (net (code "72") (name "/TA1") (class "Default")
      (node (ref "JP5") (pin "1") (pinfunction "1_1") (pintype "passive"))
      (node (ref "JP9") (pin "1") (pinfunction "1_1") (pintype "passive"))
      (node (ref "U3") (pin "7") (pinfunction "BO2_7") (pintype "passive"))
    )
    (net (code "73") (name "/TA2") (class "Default")
      (node (ref "JP5") (pin "6") (pinfunction "6_6") (pintype "passive"))
      (node (ref "JP9") (pin "6") (pinfunction "6_6") (pintype "passive"))
      (node (ref "U3") (pin "6") (pinfunction "BO1_6") (pintype "passive"))
    )
    (net (code "74") (name "/TB1") (class "Default")
      (node (ref "JP10") (pin "1") (pinfunction "1_1") (pintype "passive"))
      (node (ref "JP6") (pin "1") (pinfunction "1_1") (pintype "passive"))
      (node (ref "U3") (pin "5") (pinfunction "AO2_5") (pintype "passive"))
    )
    (net (code "75") (name "/TB2") (class "Default")
      (node (ref "JP10") (pin "6") (pinfunction "6_6") (pintype "passive"))
      (node (ref "JP6") (pin "6") (pinfunction "6_6") (pintype "passive"))
      (node (ref "U3") (pin "4") (pinfunction "AO1_4") (pintype "passive"))
    )
    (net (code "76") (name "/TC1") (class "Default")
      (node (ref "JP11") (pin "1") (pinfunction "1_1") (pintype "passive"))
      (node (ref "JP7") (pin "1") (pinfunction "1_1") (pintype "passive"))
      (node (ref "U5") (pin "7") (pinfunction "BO2_7") (pintype "passive"))
    )
    (net (code "77") (name "/TC2") (class "Default")
      (node (ref "JP11") (pin "6") (pinfunction "6_6") (pintype "passive"))
      (node (ref "JP7") (pin "6") (pinfunction "6_6") (pintype "passive"))
      (node (ref "U5") (pin "6") (pinfunction "BO1_6") (pintype "passive"))
    )
    (net (code "78") (name "/TD1") (class "Default")
      (node (ref "JP12") (pin "1") (pinfunction "1_1") (pintype "passive"))
      (node (ref "JP8") (pin "1") (pinfunction "1_1") (pintype "passive"))
      (node (ref "U5") (pin "5") (pinfunction "AO2_5") (pintype "passive"))
    )
    (net (code "79") (name "/TD2") (class "Default")
      (node (ref "JP12") (pin "6") (pinfunction "6_6") (pintype "passive"))
      (node (ref "JP8") (pin "6") (pinfunction "6_6") (pintype "passive"))
      (node (ref "U5") (pin "4") (pinfunction "AO1_4") (pintype "passive"))
    )
    (net (code "80") (name "3V3") (class "Default")
      (node (ref "C1") (pin "1") (pinfunction "1_1") (pintype "passive"))
      (node (ref "C10") (pin "2") (pinfunction "2_2") (pintype "passive"))
      (node (ref "C2") (pin "1") (pinfunction "1_1") (pintype "passive"))
      (node (ref "C9") (pin "2") (pinfunction "2_2") (pintype "passive"))
      (node (ref "JP13") (pin "2") (pinfunction "2_2") (pintype "passive"))
      (node (ref "JP14") (pin "1") (pinfunction "1_1") (pintype "passive"))
      (node (ref "JP16") (pin "3") (pinfunction "3_3") (pintype "passive"))
      (node (ref "JP16") (pin "4") (pinfunction "4_4") (pintype "passive"))
      (node (ref "JP17") (pin "1") (pinfunction "1_1") (pintype "passive"))
      (node (ref "JP18") (pin "1") (pinfunction "1_1") (pintype "passive"))
      (node (ref "JP19") (pin "1") (pinfunction "1_1") (pintype "passive"))
      (node (ref "JP27") (pin "1") (pinfunction "1_1") (pintype "passive"))
      (node (ref "JP27") (pin "2") (pinfunction "2_2") (pintype "passive"))
      (node (ref "U1") (pin "1") (pinfunction "3V3_1") (pintype "passive"))
      (node (ref "U1") (pin "55") (pinfunction "3V3_55") (pintype "passive"))
      (node (ref "U1") (pin "56") (pinfunction "3V3_56") (pintype "passive"))
      (node (ref "U2") (pin "1") (pinfunction "DIR_1") (pintype "passive"))
      (node (ref "U2") (pin "20") (pinfunction "VCC_20") (pintype "passive"))
      (node (ref "U4") (pin "1") (pinfunction "DIR_1") (pintype "passive"))
      (node (ref "U4") (pin "20") (pinfunction "VCC_20") (pintype "passive"))
      (node (ref "U6") (pin "2") (pinfunction "2_2") (pintype "passive"))
    )
    (net (code "81") (name "GND") (class "Default")
      (node (ref "C1") (pin "2") (pinfunction "2_2") (pintype "passive"))
      (node (ref "C10") (pin "1") (pinfunction "1_1") (pintype "passive"))
      (node (ref "C2") (pin "2") (pinfunction "2_2") (pintype "passive"))
      (node (ref "C3") (pin "2") (pinfunction "2_2") (pintype "passive"))
      (node (ref "C4") (pin "2") (pinfunction "2_2") (pintype "passive"))
      (node (ref "C5") (pin "2") (pinfunction "2_2") (pintype "passive"))
      (node (ref "C6") (pin "2") (pinfunction "2_2") (pintype "passive"))
      (node (ref "C7") (pin "1") (pinfunction "1_1") (pintype "passive"))
      (node (ref "C8") (pin "1") (pinfunction "1_1") (pintype "passive"))
      (node (ref "C9") (pin "1") (pinfunction "1_1") (pintype "passive"))
      (node (ref "D2") (pin "1") (pinfunction "A_1") (pintype "passive"))
      (node (ref "D3") (pin "1") (pinfunction "A_1") (pintype "passive"))
      (node (ref "D4") (pin "1") (pinfunction "A_1") (pintype "passive"))
      (node (ref "J1") (pin "2") (pinfunction "GND_2") (pintype "passive"))
      (node (ref "JP10") (pin "2") (pinfunction "2_2") (pintype "passive"))
      (node (ref "JP11") (pin "2") (pinfunction "2_2") (pintype "passive"))
      (node (ref "JP12") (pin "2") (pinfunction "2_2") (pintype "passive"))
      (node (ref "JP13") (pin "1") (pinfunction "1_1") (pintype "passive"))
      (node (ref "JP14") (pin "4") (pinfunction "4_4") (pintype "passive"))
      (node (ref "JP15") (pin "2") (pinfunction "2_2") (pintype "passive"))
      (node (ref "JP16") (pin "1") (pinfunction "1_1") (pintype "passive"))
      (node (ref "JP16") (pin "2") (pinfunction "2_2") (pintype "passive"))
      (node (ref "JP17") (pin "2") (pinfunction "2_2") (pintype "passive"))
      (node (ref "JP17") (pin "7") (pinfunction "7_7") (pintype "passive"))
      (node (ref "JP18") (pin "2") (pinfunction "2_2") (pintype "passive"))
      (node (ref "JP19") (pin "2") (pinfunction "2_2") (pintype "passive"))
      (node (ref "JP20") (pin "1") (pinfunction "1_1") (pintype "passive"))
      (node (ref "JP21") (pin "1") (pinfunction "1_1") (pintype "passive"))
      (node (ref "JP22") (pin "1") (pinfunction "1_1") (pintype "passive"))
      (node (ref "JP23") (pin "1") (pinfunction "1_1") (pintype "passive"))
      (node (ref "JP26") (pin "1") (pinfunction "1_1") (pintype "passive"))
      (node (ref "JP26") (pin "2") (pinfunction "2_2") (pintype "passive"))
      (node (ref "JP29") (pin "1") (pinfunction "1_1") (pintype "passive"))
      (node (ref "JP29") (pin "2") (pinfunction "2_2") (pintype "passive"))
      (node (ref "JP3") (pin "1") (pinfunction "1_1") (pintype "passive"))
      (node (ref "JP3") (pin "2") (pinfunction "2_2") (pintype "passive"))
      (node (ref "JP4") (pin "1") (pinfunction "1_1") (pintype "passive"))
      (node (ref "JP4") (pin "2") (pinfunction "2_2") (pintype "passive"))
      (node (ref "JP5") (pin "2") (pinfunction "2_2") (pintype "passive"))
      (node (ref "JP6") (pin "2") (pinfunction "2_2") (pintype "passive"))
      (node (ref "JP7") (pin "2") (pinfunction "2_2") (pintype "passive"))
      (node (ref "JP8") (pin "2") (pinfunction "2_2") (pintype "passive"))
      (node (ref "JP9") (pin "2") (pinfunction "2_2") (pintype "passive"))
      (node (ref "U1") (pin "4") (pinfunction "GND_4") (pintype "passive"))
      (node (ref "U1") (pin "57") (pinfunction "GND_57") (pintype "passive"))
      (node (ref "U1") (pin "58") (pinfunction "GND_58") (pintype "passive"))
      (node (ref "U1") (pin "77") (pinfunction "GND_77") (pintype "passive"))
      (node (ref "U2") (pin "10") (pinfunction "GND_10") (pintype "passive"))
      (node (ref "U2") (pin "11") (pinfunction "B8_11") (pintype "passive"))
      (node (ref "U2") (pin "12") (pinfunction "B7_12") (pintype "passive"))
      (node (ref "U2") (pin "19") (pinfunction "OE#_19") (pintype "passive"))
      (node (ref "U2") (pin "8") (pinfunction "A7_8") (pintype "passive"))
      (node (ref "U2") (pin "9") (pinfunction "A8_9") (pintype "passive"))
      (node (ref "U3") (pin "3") (pinfunction "GND_3") (pintype "passive"))
      (node (ref "U3") (pin "8") (pinfunction "GND_8") (pintype "passive"))
      (node (ref "U3") (pin "9") (pinfunction "GND_9") (pintype "passive"))
      (node (ref "U4") (pin "10") (pinfunction "GND_10") (pintype "passive"))
      (node (ref "U4") (pin "11") (pinfunction "B8_11") (pintype "passive"))
      (node (ref "U4") (pin "12") (pinfunction "B7_12") (pintype "passive"))
      (node (ref "U4") (pin "19") (pinfunction "OE#_19") (pintype "passive"))
      (node (ref "U4") (pin "8") (pinfunction "A7_8") (pintype "passive"))
      (node (ref "U4") (pin "9") (pinfunction "A8_9") (pintype "passive"))
      (node (ref "U5") (pin "3") (pinfunction "GND_3") (pintype "passive"))
      (node (ref "U5") (pin "8") (pinfunction "GND_8") (pintype "passive"))
      (node (ref "U5") (pin "9") (pinfunction "GND_9") (pintype "passive"))
      (node (ref "U6") (pin "1") (pinfunction "1_1") (pintype "passive"))
    )
    (net (code "82") (name "Net-(D1-A)") (class "Default")
      (node (ref "D1") (pin "1") (pinfunction "A_1") (pintype "passive"))
      (node (ref "JP2") (pin "1") (pinfunction "1_1") (pintype "passive"))
      (node (ref "JP2") (pin "2") (pinfunction "2_2") (pintype "passive"))
    )
    (net (code "83") (name "Net-(J1-VCC)") (class "Default")
      (node (ref "J1") (pin "1") (pinfunction "VCC_1") (pintype "passive"))
      (node (ref "S1") (pin "2") (pinfunction "2_2") (pintype "passive"))
    )
    (net (code "84") (name "Net-(U2-B1)") (class "Default")
      (node (ref "U2") (pin "18") (pinfunction "B1_18") (pintype "passive"))
      (node (ref "U3") (pin "10") (pinfunction "PWMB_10") (pintype "passive"))
    )
    (net (code "85") (name "Net-(U2-B2)") (class "Default")
      (node (ref "U2") (pin "17") (pinfunction "B2_17") (pintype "passive"))
      (node (ref "U3") (pin "11") (pinfunction "BIN2_11") (pintype "passive"))
    )
    (net (code "86") (name "Net-(U2-B3)") (class "Default")
      (node (ref "U2") (pin "16") (pinfunction "B3_16") (pintype "passive"))
      (node (ref "U3") (pin "12") (pinfunction "BIN1_12") (pintype "passive"))
    )
    (net (code "87") (name "Net-(U2-B4)") (class "Default")
      (node (ref "U2") (pin "15") (pinfunction "B4_15") (pintype "passive"))
      (node (ref "U3") (pin "14") (pinfunction "AIN1_14") (pintype "passive"))
    )
    (net (code "88") (name "Net-(U2-B5)") (class "Default")
      (node (ref "U2") (pin "14") (pinfunction "B5_14") (pintype "passive"))
      (node (ref "U3") (pin "15") (pinfunction "AIN2_15") (pintype "passive"))
    )
    (net (code "89") (name "Net-(U2-B6)") (class "Default")
      (node (ref "U2") (pin "13") (pinfunction "B6_13") (pintype "passive"))
      (node (ref "U3") (pin "16") (pinfunction "PWMA_16") (pintype "passive"))
    )
    (net (code "90") (name "Net-(U4-B1)") (class "Default")
      (node (ref "U4") (pin "18") (pinfunction "B1_18") (pintype "passive"))
      (node (ref "U5") (pin "10") (pinfunction "PWMB_10") (pintype "passive"))
    )
    (net (code "91") (name "Net-(U4-B2)") (class "Default")
      (node (ref "U4") (pin "17") (pinfunction "B2_17") (pintype "passive"))
      (node (ref "U5") (pin "11") (pinfunction "BIN2_11") (pintype "passive"))
    )
    (net (code "92") (name "Net-(U4-B3)") (class "Default")
      (node (ref "U4") (pin "16") (pinfunction "B3_16") (pintype "passive"))
      (node (ref "U5") (pin "12") (pinfunction "BIN1_12") (pintype "passive"))
    )
    (net (code "93") (name "Net-(U4-B4)") (class "Default")
      (node (ref "U4") (pin "15") (pinfunction "B4_15") (pintype "passive"))
      (node (ref "U5") (pin "14") (pinfunction "AIN1_14") (pintype "passive"))
    )
    (net (code "94") (name "Net-(U4-B5)") (class "Default")
      (node (ref "U4") (pin "14") (pinfunction "B5_14") (pintype "passive"))
      (node (ref "U5") (pin "15") (pinfunction "AIN2_15") (pintype "passive"))
    )
    (net (code "95") (name "Net-(U4-B6)") (class "Default")
      (node (ref "U4") (pin "13") (pinfunction "B6_13") (pintype "passive"))
      (node (ref "U5") (pin "16") (pinfunction "PWMA_16") (pintype "passive"))
    )
    (net (code "96") (name "unconnected-(JP17-Pad5)") (class "Default")
      (node (ref "JP17") (pin "5") (pinfunction "5_5") (pintype "passive+no_connect"))
    )
    (net (code "97") (name "unconnected-(JP17-Pad6)") (class "Default")
      (node (ref "JP17") (pin "6") (pinfunction "6_6") (pintype "passive+no_connect"))
    )
    (net (code "98") (name "unconnected-(S1-Pad1)") (class "Default")
      (node (ref "S1") (pin "1") (pinfunction "1_1") (pintype "passive"))
    )
    (net (code "99") (name "unconnected-(S2-Pad3)") (class "Default")
      (node (ref "S2") (pin "3") (pinfunction "3_3") (pintype "passive"))
    )
  )
)
